# Power_Supply.net
KiCad netlist of a schematic drawn in Altium Designer
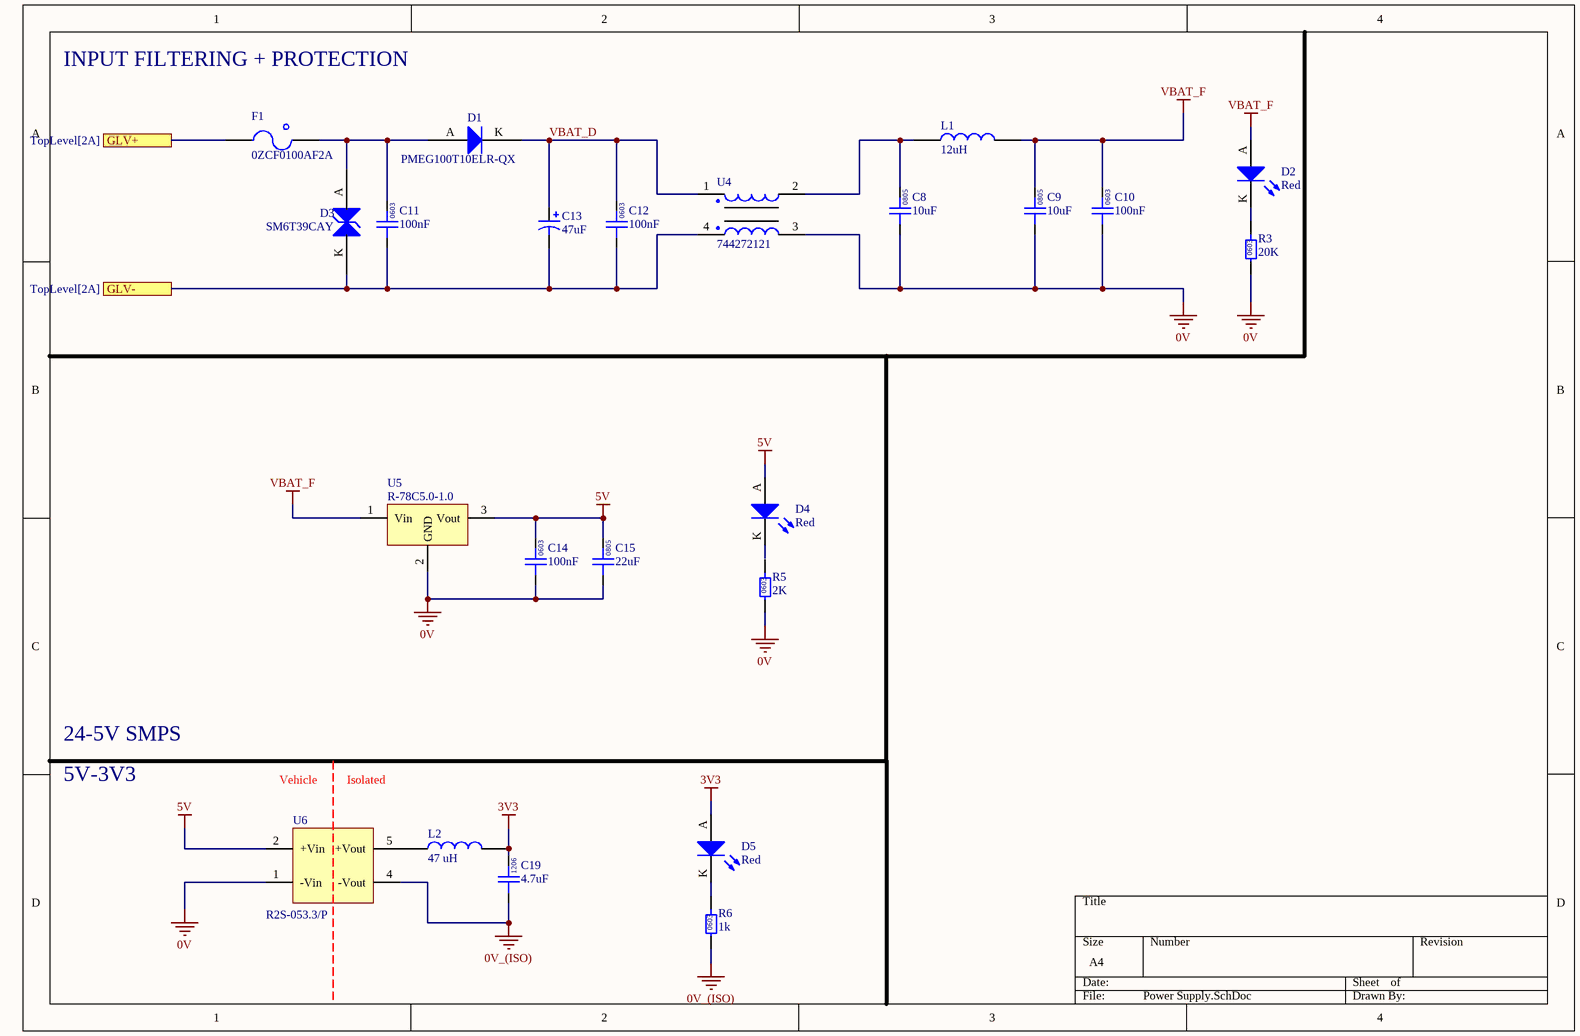
[diagram p0: Power Supply.SchDoc]

(export (version "E")
  (design (tool "Eeschema 10.0.6"))
  (components
    (comp (ref "C8")
      (value "10uF")
      (footprint "0805")
      (fields
        (field (name "PART NUMBER") "GRM21BR6YA106KE43L")
        (field (name "MANUFACTURER") "muRata")
        (field (name "TOLERANCE") "10%")
      )
      (libsource (lib "ts_standard_library") (part "Capacitor 0805"))
    )
    (comp (ref "C9")
      (value "10uF")
      (footprint "0805")
      (fields
        (field (name "PART NUMBER") "GRM21BR6YA106KE43L")
        (field (name "MANUFACTURER") "muRata")
        (field (name "TOLERANCE") "10%")
      )
      (libsource (lib "ts_standard_library") (part "Capacitor 0805"))
    )
    (comp (ref "C10")
      (value "100nF")
      (footprint "0603")
      (fields
        (field (name "PART NUMBER") "GCM188L81H104KA57D")
        (field (name "MANUFACTURER") "muRata")
        (field (name "TOLERANCE") "±10%")
      )
      (libsource (lib "ts_standard_library") (part "Capacitor 0603"))
    )
    (comp (ref "C11")
      (value "100nF")
      (footprint "0603")
      (fields
        (field (name "PART NUMBER") "GCM188L81H104KA57D")
        (field (name "MANUFACTURER") "muRata")
        (field (name "TOLERANCE") "±10%")
      )
      (libsource (lib "ts_standard_library") (part "Capacitor 0603"))
    )
    (comp (ref "C12")
      (value "100nF")
      (footprint "0603")
      (fields
        (field (name "PART NUMBER") "GCM188L81H104KA57D")
        (field (name "MANUFACTURER") "muRata")
        (field (name "TOLERANCE") "±10%")
      )
      (libsource (lib "ts_standard_library") (part "Capacitor 0603"))
    )
    (comp (ref "C13")
      (value "47uF")
      (footprint "CHEMI-CON ELCO")
      (fields (field (name "PART NUMBER") "HHXA350ARA470MF61G"))
      (libsource (lib "ts_standard_library") (part "Capacitor (Polarised)"))
    )
    (comp (ref "C14")
      (value "100nF")
      (footprint "0603")
      (fields
        (field (name "PART NUMBER") "GCM188L81H104KA57D")
        (field (name "MANUFACTURER") "muRata")
        (field (name "TOLERANCE") "±10%")
      )
      (libsource (lib "ts_standard_library") (part "Capacitor 0603"))
    )
    (comp (ref "C15")
      (value "22uF")
      (footprint "0805")
      (fields
        (field (name "PART NUMBER") "GRM21BR61A226ME51L")
        (field (name "MANUFACTURER") "muRata")
        (field (name "TOLERANCE") "20%")
      )
      (libsource (lib "ts_standard_library") (part "Capacitor 0805"))
    )
    (comp (ref "C19")
      (value "4.7uF")
      (footprint "1206 CAP")
      (fields
        (field (name "PART NUMBER") "GRM31CR71H475KA12K")
        (field (name "MANUFACTURER") "Murata Electronics")
        (field (name "TOLERANCE") "±10%")
      )
      (libsource (lib "ts_standard_library") (part "Capacitor 1206"))
    )
    (comp (ref "D1")
      (value "PMEG100T10ELR-QX")
      (footprint "SODFL350X110-2N")
      (description "Diode 100 V 1A Surface Mount SOD-123W")
      (libsource (lib "Team Swinburne") (part "PMEG100T10ELR-QX"))
    )
    (comp (ref "D2")
      (value "Red")
      (footprint "0805 LED")
      (description "Red LED Indication - Discrete 1.75V 0805 (2012 Metric)")
      (fields (field (name "PART NUMBER") "SML-210LTT86") (field (name "MANUFACTURER") "ROHM Semiconductor"))
      (libsource (lib "ts_standard_library") (part "LED"))
    )
    (comp (ref "D3")
      (value "SM6T39CAY")
      (footprint "SM6T39CAY-Footprint-1")
      (description "TVS Diode Single Bi-Dir 33.3V 600W Automotive 2-Pin SMB T/R / TVS DIODE 33.3VWM 69.7VC SMB")
      (libsource (lib "Team Swinburne") (part "SM6T39CAY-Symbol"))
    )
    (comp (ref "D4")
      (value "Red")
      (footprint "0805 LED")
      (description "Red LED Indication - Discrete 1.75V 0805 (2012 Metric)")
      (fields (field (name "PART NUMBER") "SML-210LTT86") (field (name "MANUFACTURER") "ROHM Semiconductor"))
      (libsource (lib "ts_standard_library") (part "LED"))
    )
    (comp (ref "D5")
      (value "Red")
      (footprint "0805 LED")
      (description "Red LED Indication - Discrete 1.75V 0805 (2012 Metric)")
      (fields (field (name "PART NUMBER") "SML-210LTT86") (field (name "MANUFACTURER") "ROHM Semiconductor"))
      (libsource (lib "ts_standard_library") (part "LED"))
    )
    (comp (ref "F1")
      (value "0ZCF0100AF2A")
      (footprint "2920")
      (description "PTC RESET FUSE 60V 1A 292")
      (fields
        (field (name "MANUFACTURER") "Littelfuse Inc.")
        (field (name "DIGIKEY PART NUMBER") "507-2070-1-ND")
      )
      (libsource (lib "ts_standard_library") (part "PTC Fuse"))
    )
    (comp (ref "L1")
      (value "12uH")
      (footprint "1812")
      (fields
        (field (name "PART NUMBER") "RLS-126")
        (field (name "MANUFACTURER") "Recom")
        (field (name "TOLERANCE") "0.2")
      )
      (libsource (lib "ts_standard_library") (part "Inductor"))
    )
    (comp (ref "L2")
      (value "47 uH")
      (footprint "82473C")
      (fields
        (field (name "PART NUMBER") "82473C")
        (field (name "MANUFACTURER") "Murata Power Solutions Inc.")
        (field (name "TOLERANCE") "0.1")
      )
      (libsource (lib "ts_standard_library") (part "Inductor"))
    )
    (comp (ref "R3")
      (value "20K")
      (footprint "0603")
      (fields
        (field (name "PART NUMBER") "RC0603FR-0720KL")
        (field (name "MANUFACTURER") "YAGEO")
        (field (name "TOLERANCE") "0.01")
      )
      (libsource (lib "ts_standard_library") (part "Resistor 0603"))
    )
    (comp (ref "R5")
      (value "2K")
      (footprint "0603")
      (fields
        (field (name "PART NUMBER") "RC0603FR-072KL")
        (field (name "MANUFACTURER") "YAGEO")
        (field (name "TOLERANCE") "0.01")
      )
      (libsource (lib "ts_standard_library") (part "Resistor 0603"))
    )
    (comp (ref "R6")
      (value "1k")
      (footprint "0603")
      (fields
        (field (name "PART NUMBER") "RC0603FR-071KL")
        (field (name "MANUFACTURER") "YAGEO")
        (field (name "TOLERANCE") "0.01")
      )
      (libsource (lib "ts_standard_library") (part "Resistor 0603"))
    )
    (comp (ref "U4")
      (value "744272121")
      (footprint "Wurth 4-PC Pad")
      (fields
        (field (name "MANUFACTURER") "Wurth Electronics Inc")
        (field (name "DIGIKEY PART NUMBER") "732-1489-1-ND")
      )
      (libsource (lib "ts_standard_library") (part "CM Choke"))
    )
    (comp (ref "U5")
      (value "R-78C5.0-1.0")
      (footprint "RECOM 3-SIP")
      (description "CONV DC/DC 1A 5V OUT SIP VERT")
      (fields (field (name "MANUFACTURER") "Recom") (field (name "DIGIKEY PART NUMBER") "945-1395-5-ND"))
      (libsource (lib "ts_standard_library") (part "R-78C5.0-1.0"))
    )
    (comp (ref "U6")
      (value "R2S-053.3/P")
      (footprint "RECOM 8-SMD (5 Pin)")
      (description "Isolated Module DC DC Converter 1 Output 3.3V 606mA 4.5V - 5.5V Input")
      (fields (field (name "MANUFACTURER") "Recom") (field (name "DIGIKEY PART NUMBER") "945-2677-5-ND"))
      (libsource (lib "ts_standard_library") (part "R2S-053.3/P"))
    )
  )
  (nets
    (net (code "1") (name "/GLV+") (class "Default")
      (node (ref "F1") (pin "1") (pinfunction "1_1") (pintype "passive"))
    )
    (net (code "2") (name "/GLV-") (class "Default")
      (node (ref "C11") (pin "1") (pinfunction "1_1") (pintype "passive"))
      (node (ref "C12") (pin "1") (pinfunction "1_1") (pintype "passive"))
      (node (ref "C13") (pin "1") (pinfunction "1_1") (pintype "passive"))
      (node (ref "D3") (pin "K") (pintype "passive"))
      (node (ref "U4") (pin "4") (pinfunction "4_4") (pintype "passive"))
    )
    (net (code "3") (name "/VBAT_D") (class "Default")
      (node (ref "C12") (pin "2") (pinfunction "2_2") (pintype "passive"))
      (node (ref "C13") (pin "2") (pinfunction "2_2") (pintype "passive"))
      (node (ref "D1") (pin "K") (pintype "passive"))
      (node (ref "U4") (pin "1") (pinfunction "1_1") (pintype "passive"))
    )
    (net (code "4") (name "0V") (class "Default")
      (node (ref "C10") (pin "1") (pinfunction "1_1") (pintype "passive"))
      (node (ref "C14") (pin "1") (pinfunction "1_1") (pintype "passive"))
      (node (ref "C15") (pin "1") (pinfunction "1_1") (pintype "passive"))
      (node (ref "C8") (pin "1") (pinfunction "1_1") (pintype "passive"))
      (node (ref "C9") (pin "1") (pinfunction "1_1") (pintype "passive"))
      (node (ref "R3") (pin "1") (pinfunction "1_1") (pintype "passive"))
      (node (ref "R5") (pin "1") (pinfunction "1_1") (pintype "passive"))
      (node (ref "U4") (pin "3") (pinfunction "3_3") (pintype "power_in"))
      (node (ref "U5") (pin "2") (pinfunction "GND_2") (pintype "passive"))
      (node (ref "U6") (pin "1") (pinfunction "-Vin_1") (pintype "power_in"))
    )
    (net (code "5") (name "0V_(ISO)") (class "Default")
      (node (ref "C19") (pin "1") (pinfunction "1_1") (pintype "passive"))
      (node (ref "R6") (pin "1") (pinfunction "1_1") (pintype "passive"))
      (node (ref "U6") (pin "4") (pinfunction "-Vout_4") (pintype "power_in"))
    )
    (net (code "6") (name "3V3") (class "Default")
      (node (ref "C19") (pin "2") (pinfunction "2_2") (pintype "passive"))
      (node (ref "D5") (pin "A") (pinfunction "A_A") (pintype "passive"))
      (node (ref "L2") (pin "1") (pinfunction "1_1") (pintype "passive"))
    )
    (net (code "7") (name "5V") (class "Default")
      (node (ref "C14") (pin "2") (pinfunction "2_2") (pintype "passive"))
      (node (ref "C15") (pin "2") (pinfunction "2_2") (pintype "passive"))
      (node (ref "D4") (pin "A") (pinfunction "A_A") (pintype "passive"))
      (node (ref "U5") (pin "3") (pinfunction "Vout_3") (pintype "passive"))
      (node (ref "U6") (pin "2") (pinfunction "+Vin_2") (pintype "power_in"))
    )
    (net (code "8") (name "Net-(C8-Pad2)") (class "Default")
      (node (ref "C8") (pin "2") (pinfunction "2_2") (pintype "passive"))
      (node (ref "L1") (pin "2") (pinfunction "2_2") (pintype "passive"))
      (node (ref "U4") (pin "2") (pinfunction "2_2") (pintype "passive"))
    )
    (net (code "9") (name "Net-(C11-Pad2)") (class "Default")
      (node (ref "C11") (pin "2") (pinfunction "2_2") (pintype "passive"))
      (node (ref "D1") (pin "A") (pintype "passive"))
      (node (ref "D3") (pin "A") (pintype "passive"))
      (node (ref "F1") (pin "2") (pinfunction "2_2") (pintype "passive"))
    )
    (net (code "10") (name "Net-(D2-PadK)") (class "Default")
      (node (ref "D2") (pin "K") (pinfunction "K_K") (pintype "passive"))
      (node (ref "R3") (pin "2") (pinfunction "2_2") (pintype "passive"))
    )
    (net (code "11") (name "Net-(D5-PadK)") (class "Default")
      (node (ref "D5") (pin "K") (pinfunction "K_K") (pintype "passive"))
      (node (ref "R6") (pin "2") (pinfunction "2_2") (pintype "passive"))
    )
    (net (code "12") (name "Net-(U6-+Vout)") (class "Default")
      (node (ref "L2") (pin "2") (pinfunction "2_2") (pintype "passive"))
      (node (ref "U6") (pin "5") (pinfunction "+Vout_5") (pintype "power_in"))
    )
    (net (code "13") (name "VBAT_F") (class "Default")
      (node (ref "C10") (pin "2") (pinfunction "2_2") (pintype "passive"))
      (node (ref "C9") (pin "2") (pinfunction "2_2") (pintype "passive"))
      (node (ref "D2") (pin "A") (pinfunction "A_A") (pintype "passive"))
      (node (ref "L1") (pin "1") (pinfunction "1_1") (pintype "passive"))
      (node (ref "U5") (pin "1") (pinfunction "Vin_1") (pintype "passive"))
    )
    (net (code "14") (name "unconnected-(D4-PadK)") (class "Default")
      (node (ref "D4") (pin "K") (pinfunction "K_K") (pintype "passive"))
    )
    (net (code "15") (name "unconnected-(R5-Pad2)") (class "Default")
      (node (ref "R5") (pin "2") (pinfunction "2_2") (pintype "passive"))
    )
  )
)
